# Water_Tank_V6_1_2020-12-28_12-10-16.net
KiCad netlist of a schematic drawn in EasyEDA
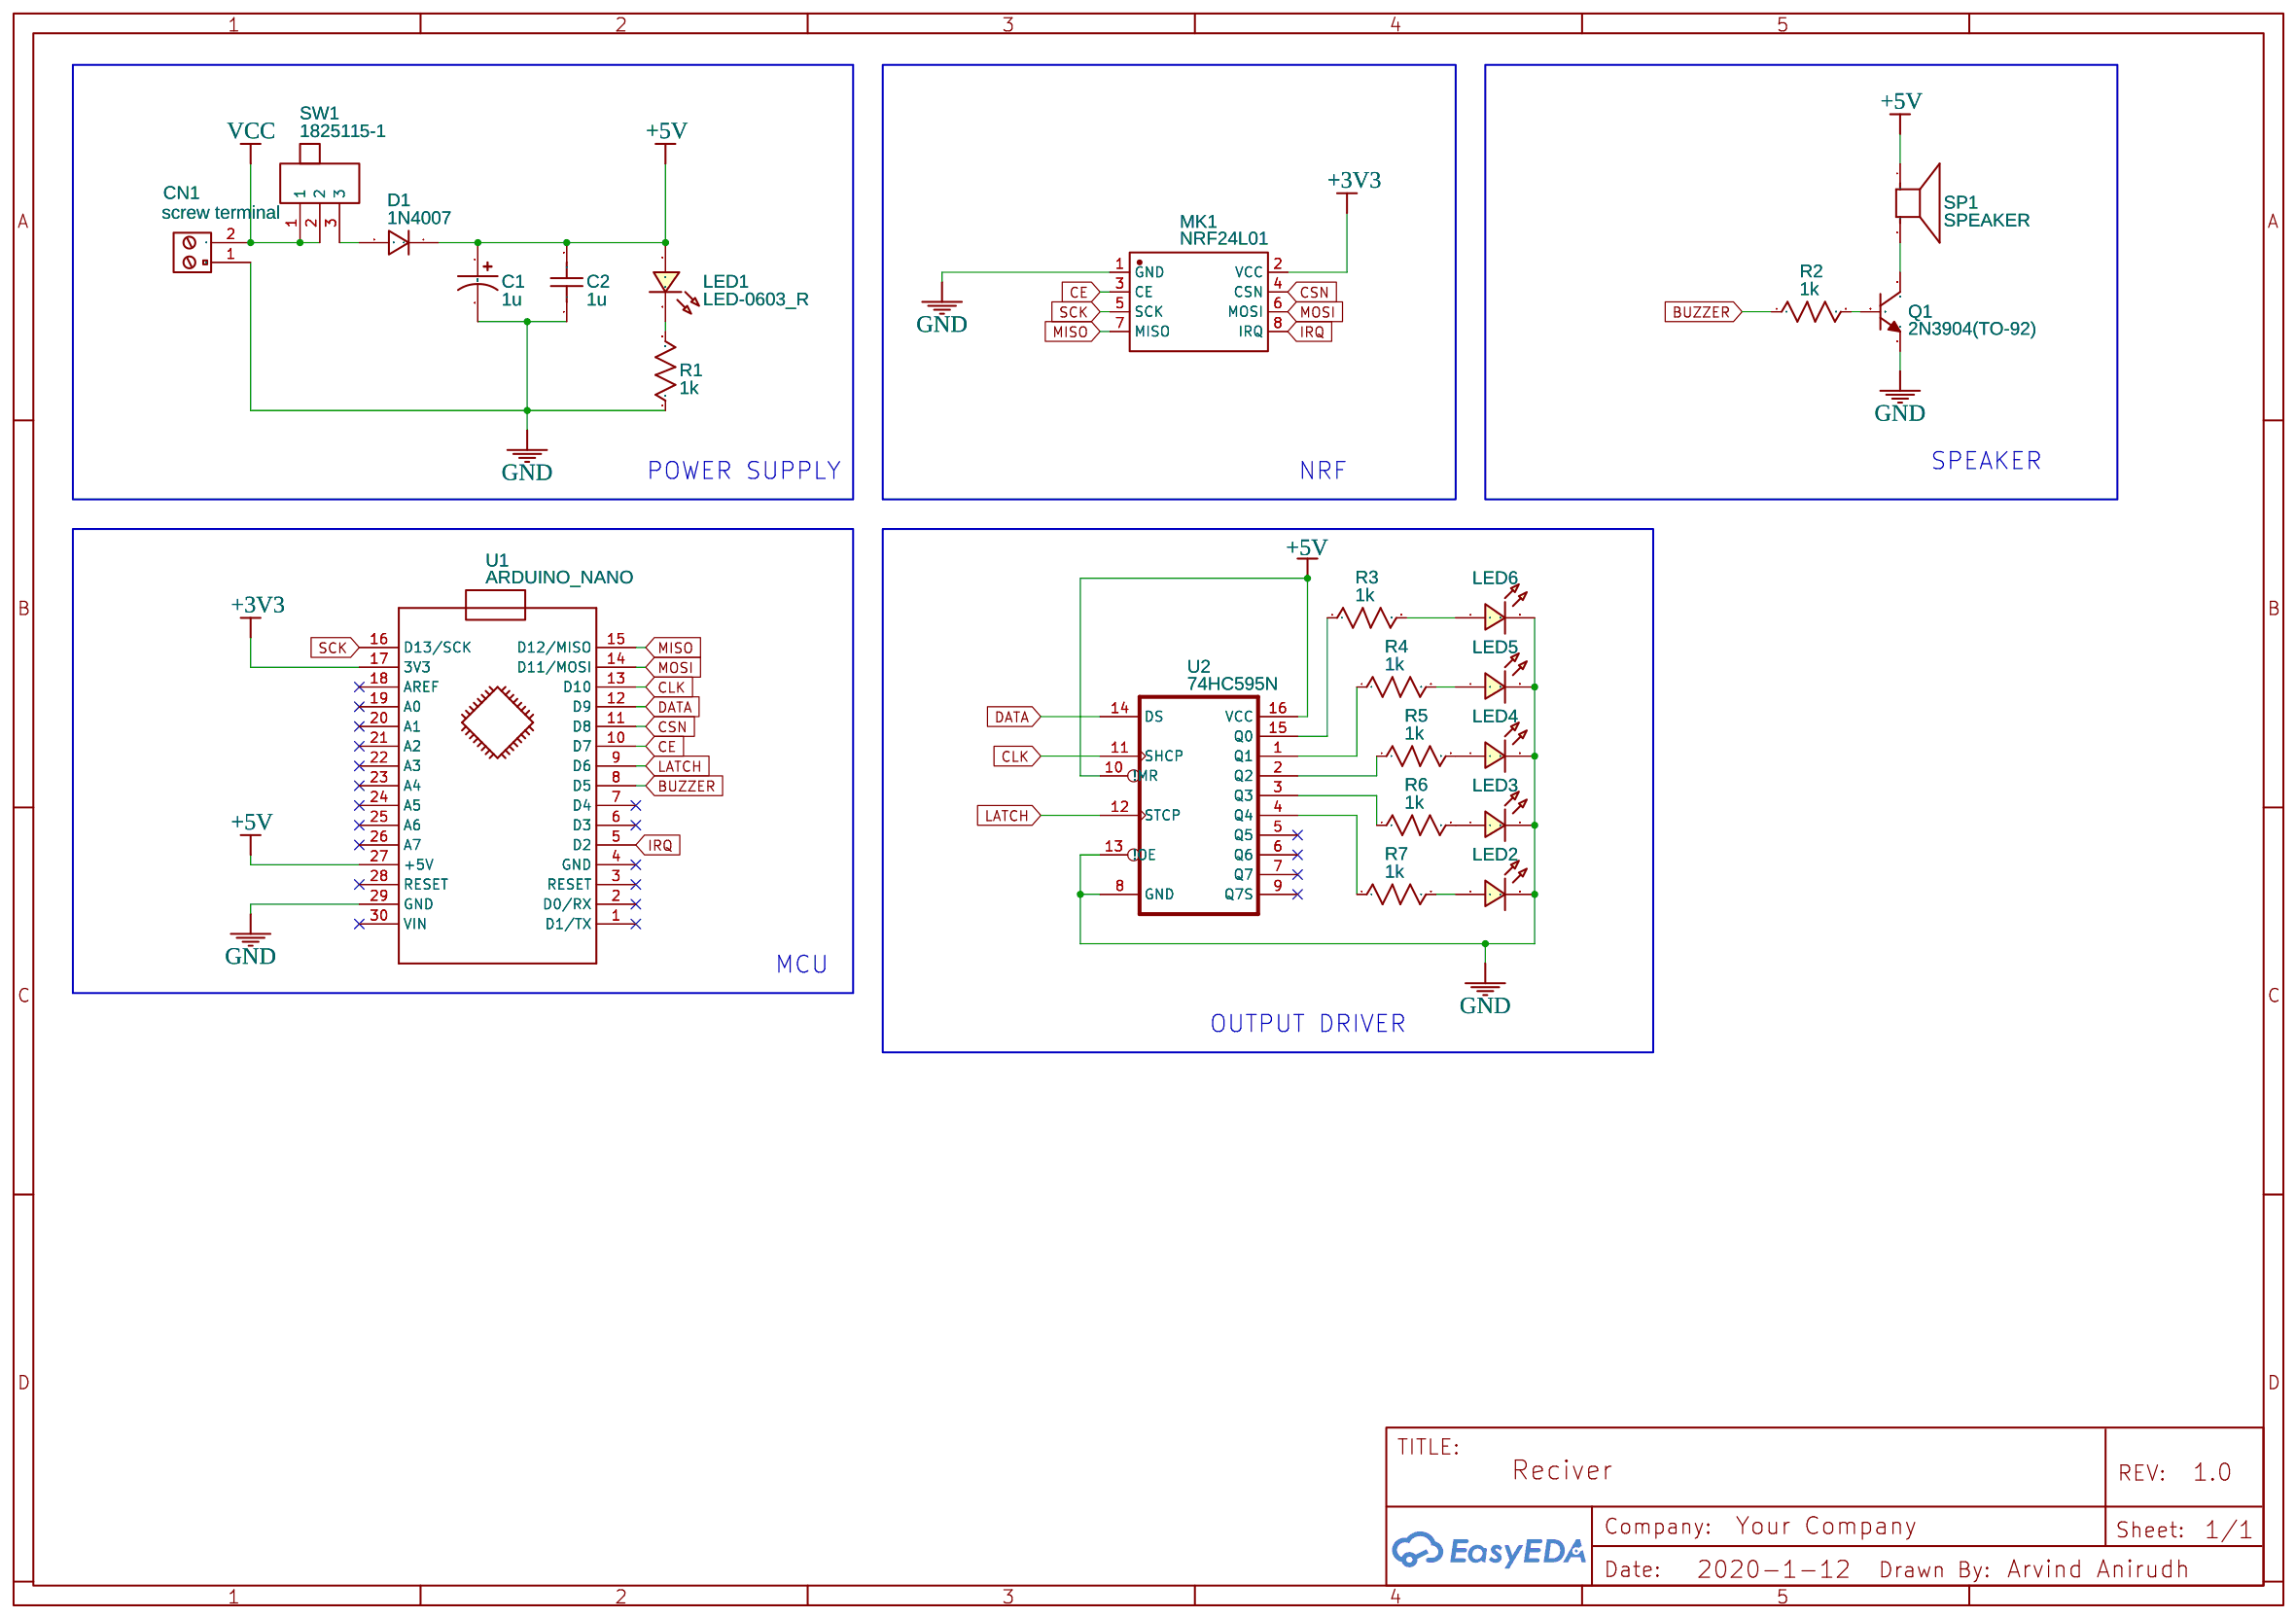
[diagram p0: Reciver]
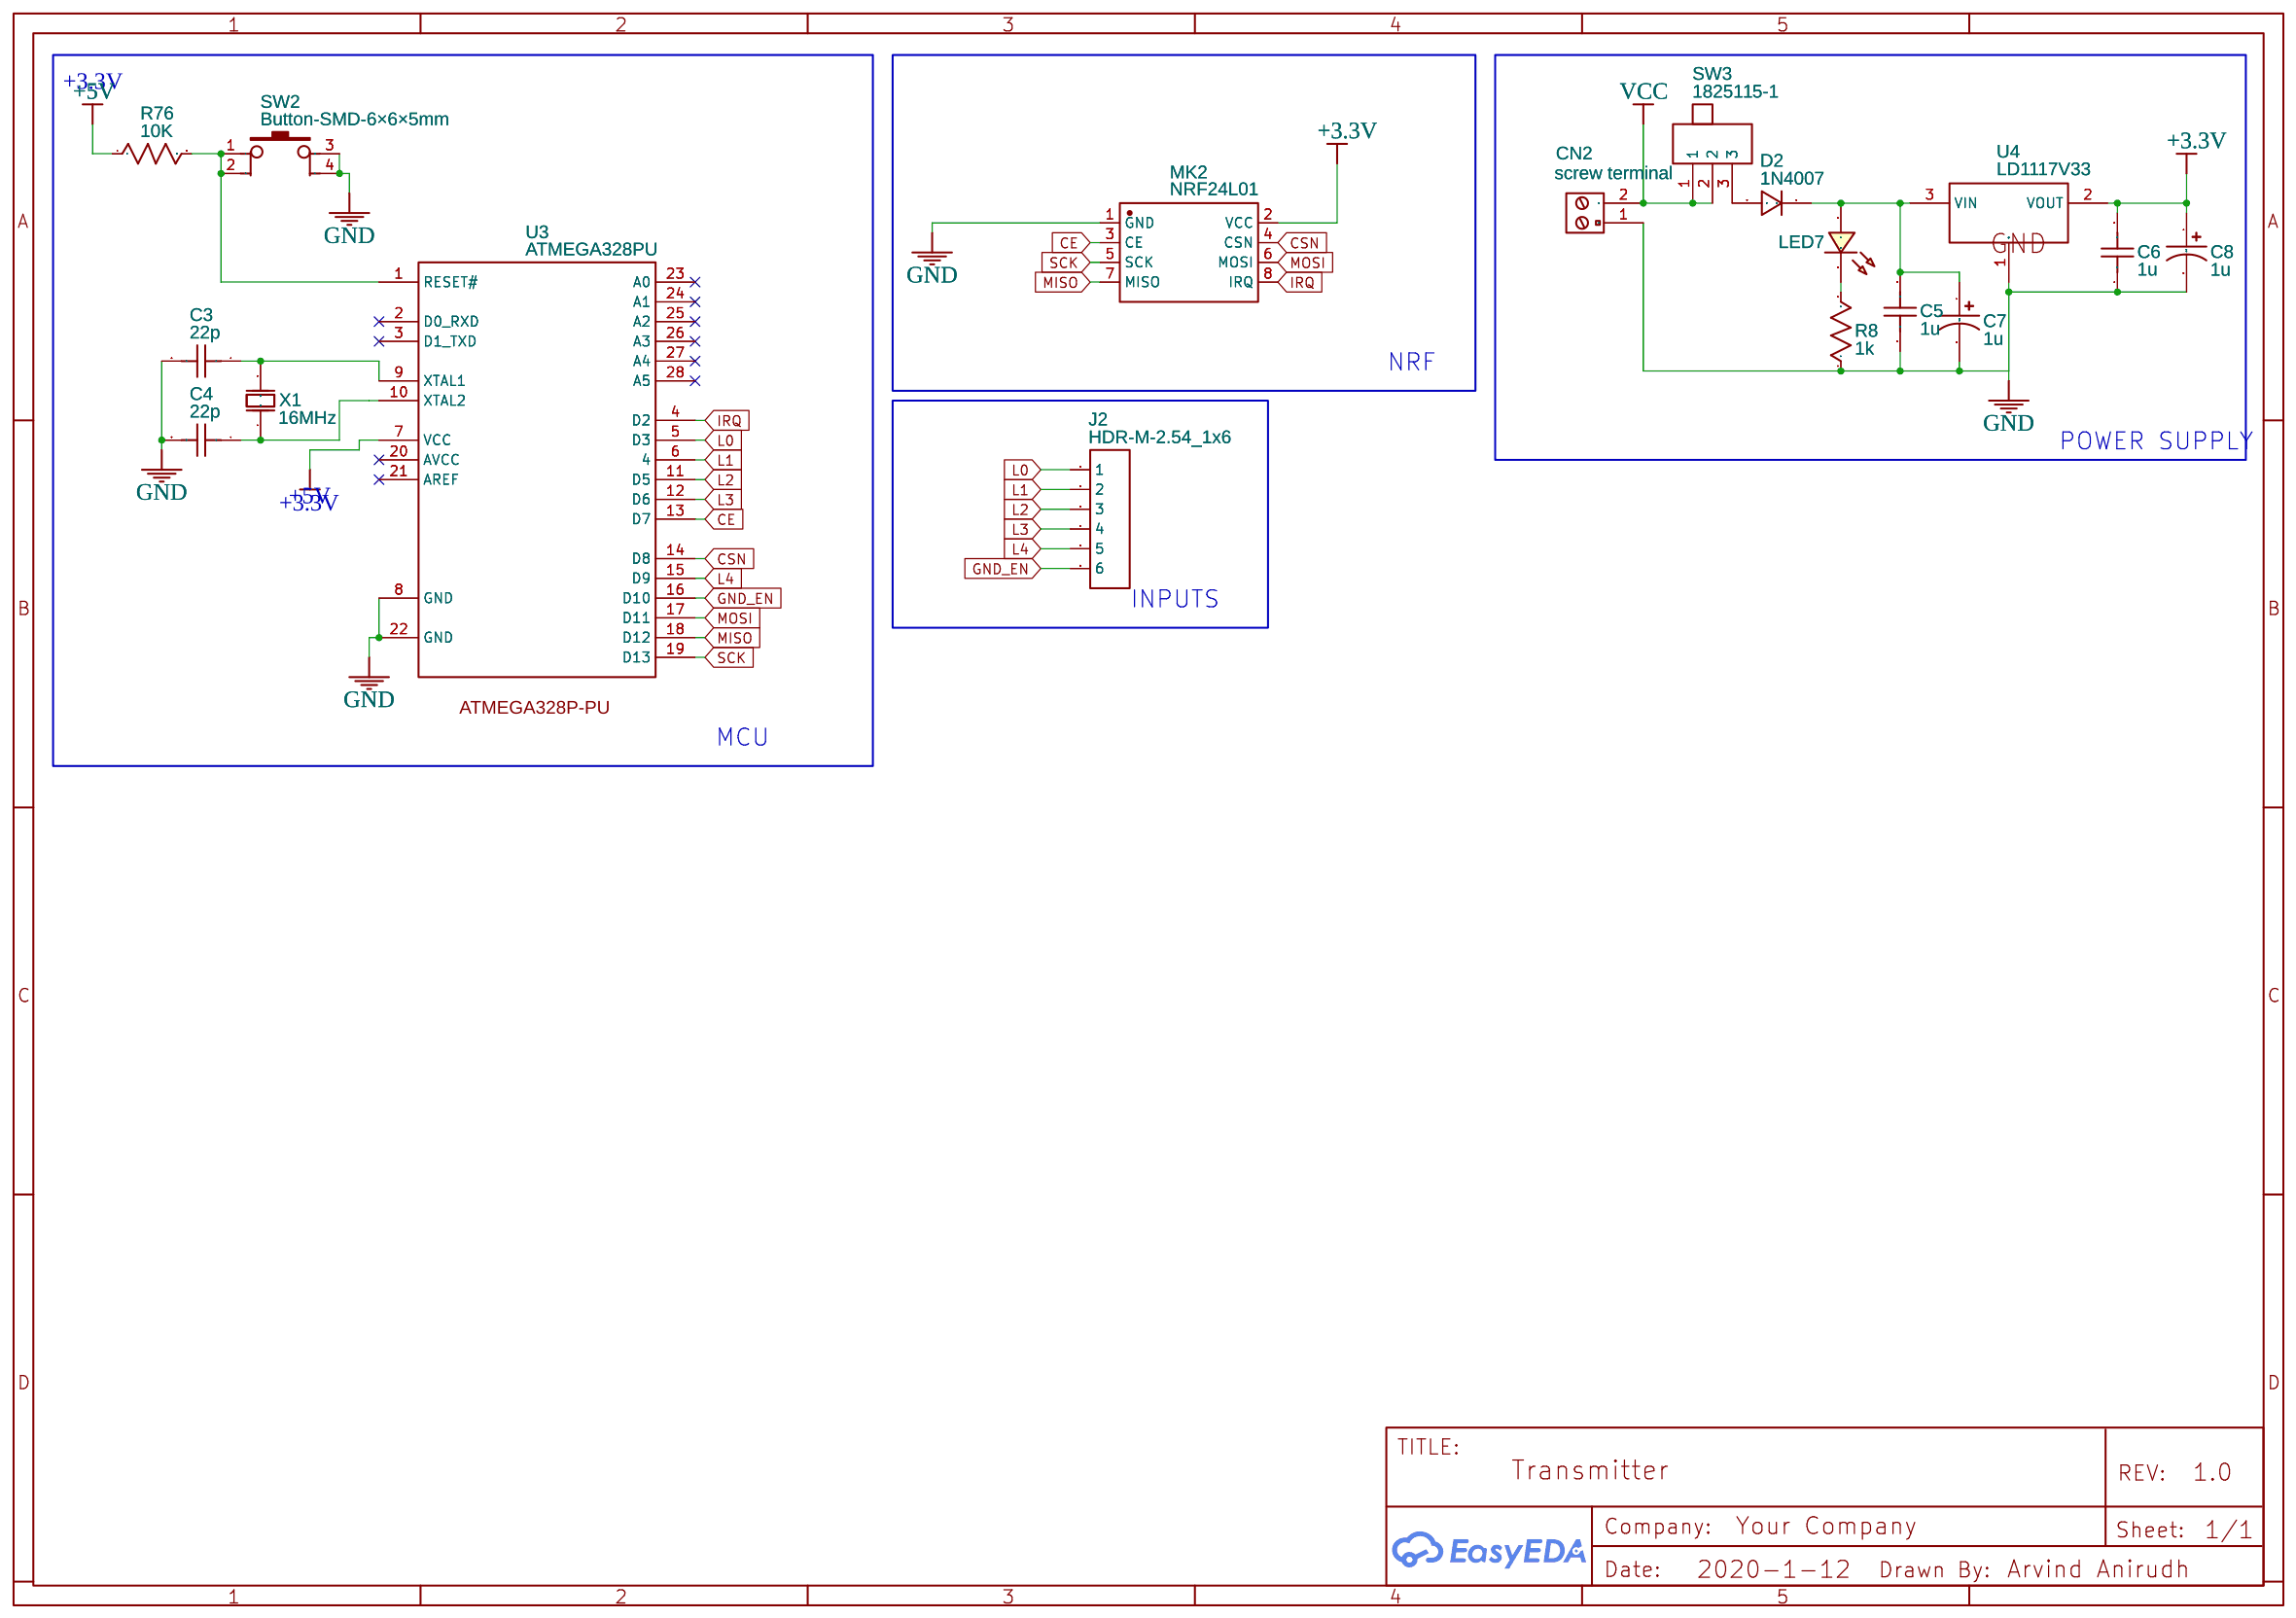
[diagram p1: Transmitter]

(export (version "E")
  (design (tool "Eeschema 10.0.6"))
  (components
    (comp (ref "C1") (value "1u") (libsource (lib "") (part "CE_TH_D4.0×F1.5_US")))
    (comp (ref "C2") (value "1u") (libsource (lib "") (part "C_RAD-0.1_US")))
    (comp (ref "CN1")
      (value "screw terminal")
      (fields (field (name "BOM_Supplier Part") "KF350-2P"))
      (libsource (lib "") (part "KF350-2P 3.5mm screw terminal"))
    )
    (comp (ref "D1")
      (value "1N4007")
      (fields (field (name "BOM_Supplier Part") "C106903"))
      (libsource (lib "") (part "1N4007"))
    )
    (comp (ref "LED1")
      (value "LED-0603_R")
      (fields
        (field (name "BOM_Manufacturer Part") "19-217/R6C-AL1M2VY/3T")
        (field (name "BOM_Supplier Part") "C72044")
      )
      (libsource (lib "") (part "LED-0603_R"))
    )
    (comp (ref "LED2")
      (value "LED-TH-3mm_R")
      (fields
        (field (name "BOM_Manufacturer Part") "204-10SDRD/S530-A3-L")
        (field (name "BOM_Supplier Part") "C84774")
      )
      (libsource (lib "") (part "LED-TH-3mm_R"))
    )
    (comp (ref "LED3")
      (value "LED-TH-3mm_G")
      (fields
        (field (name "BOM_Manufacturer Part") "204-10SYGD/S530-E3")
        (field (name "BOM_Supplier Part") "C85161")
      )
      (libsource (lib "") (part "LED-TH-3mm_G"))
    )
    (comp (ref "LED4")
      (value "LED-TH-3mm_G")
      (fields
        (field (name "BOM_Manufacturer Part") "204-10SYGD/S530-E3")
        (field (name "BOM_Supplier Part") "C85161")
      )
      (libsource (lib "") (part "LED-TH-3mm_G"))
    )
    (comp (ref "LED5")
      (value "LED-TH-3mm_G")
      (fields
        (field (name "BOM_Manufacturer Part") "204-10SYGD/S530-E3")
        (field (name "BOM_Supplier Part") "C85161")
      )
      (libsource (lib "") (part "LED-TH-3mm_G"))
    )
    (comp (ref "LED6")
      (value "LED-TH-3mm_B")
      (fields
        (field (name "BOM_Manufacturer Part") "204-10SUBC/S400-A4")
        (field (name "BOM_Supplier Part") "C86881")
      )
      (libsource (lib "") (part "LED-TH-3mm_B"))
    )
    (comp (ref "MK1")
      (value "NRF24L01")
      (fields
        (field (name "BOM_Manufacturer Part") "NRF24L01+功率加强版绑定2.4Gwireless module")
        (field (name "BOM_Supplier Part") "C90751")
      )
      (libsource (lib "") (part "NRF24L01"))
    )
    (comp (ref "Q1")
      (value "2N3904(TO-92)")
      (fields (field (name "BOM_Manufacturer Part") "2N3904") (field (name "BOM_Supplier Part") "C118538"))
      (libsource (lib "") (part "2N3904(TO-92)"))
    )
    (comp (ref "R1") (value "1k") (libsource (lib "") (part "R_AXIAL-0.4_US_1")))
    (comp (ref "R2") (value "1k") (libsource (lib "") (part "R_AXIAL-0.4_US")))
    (comp (ref "R3") (value "1k") (libsource (lib "") (part "R_AXIAL-0.4_US")))
    (comp (ref "R4") (value "1k") (libsource (lib "") (part "R_AXIAL-0.4_US")))
    (comp (ref "R5") (value "1k") (libsource (lib "") (part "R_AXIAL-0.4_US")))
    (comp (ref "R6") (value "1k") (libsource (lib "") (part "R_AXIAL-0.4_US")))
    (comp (ref "R7") (value "1k") (libsource (lib "") (part "R_AXIAL-0.4_US")))
    (comp (ref "SP1") (value "SPEAKER") (libsource (lib "") (part "SPEAKER")))
    (comp (ref "SW1")
      (value "1825115-1")
      (fields (field (name "BOM_Supplier Part") "C266201"))
      (libsource (lib "") (part "1825115-1"))
    )
    (comp (ref "U1") (value "ARDUINO_NANO") (libsource (lib "") (part "ARDUINO_NANO")))
    (comp (ref "U2") (value "74HC595N") (libsource (lib "") (part "74HC595N")))
    (comp (ref "C3") (value "22p") (libsource (lib "") (part "C_RAD-0.1_US_1")))
    (comp (ref "C4") (value "22p") (libsource (lib "") (part "C_RAD-0.1_US_1")))
    (comp (ref "C5") (value "1u") (libsource (lib "") (part "C_RAD-0.1_US")))
    (comp (ref "C6") (value "1u") (libsource (lib "") (part "C_RAD-0.1_US")))
    (comp (ref "C7") (value "1u") (libsource (lib "") (part "CE_TH_D4.0×F1.5_US")))
    (comp (ref "C8") (value "1u") (libsource (lib "") (part "CE_TH_D4.0×F1.5_US_1")))
    (comp (ref "CN2")
      (value "screw terminal")
      (fields (field (name "BOM_Supplier Part") "KF350-2P"))
      (libsource (lib "") (part "KF350-2P 3.5mm screw terminal"))
    )
    (comp (ref "D2")
      (value "1N4007")
      (fields (field (name "BOM_Supplier Part") "C106903"))
      (libsource (lib "") (part "1N4007"))
    )
    (comp (ref "J2")
      (value "HDR-M-2.54_1x6")
      (fields (field (name "BOM_Supplier Part") "C190819"))
      (libsource (lib "") (part "HDR-M-2.54_1x6"))
    )
    (comp (ref "LED7")
      (value "LED-0603_R")
      (fields
        (field (name "BOM_Manufacturer Part") "19-217/R6C-AL1M2VY/3T")
        (field (name "BOM_Supplier Part") "C72044")
      )
      (libsource (lib "") (part "LED-0603_R"))
    )
    (comp (ref "MK2")
      (value "NRF24L01")
      (fields
        (field (name "BOM_Manufacturer Part") "NRF24L01+功率加强版绑定2.4Gwireless module")
        (field (name "BOM_Supplier Part") "C90751")
      )
      (libsource (lib "") (part "NRF24L01"))
    )
    (comp (ref "R8") (value "1k") (libsource (lib "") (part "R_AXIAL-0.4_US")))
    (comp (ref "R76") (value "10K") (libsource (lib "") (part "Res_0805(1/8W)_US")))
    (comp (ref "SW2")
      (value "Button-SMD-6×6×5mm")
      (fields
        (field (name "BOM_Manufacturer Part") "6×6×5mm RHOS")
        (field (name "BOM_Supplier Part") "C21456")
      )
      (libsource (lib "") (part "Button-SMD-6×6×5mm"))
    )
    (comp (ref "SW3")
      (value "1825115-1")
      (fields (field (name "BOM_Supplier Part") "C266201"))
      (libsource (lib "") (part "1825115-1"))
    )
    (comp (ref "U3")
      (value "ATMEGA328PU")
      (fields
        (field (name "BOM_Manufacturer Part") "ATMEGA328P-PU")
        (field (name "BOM_Supplier Part") "C33901")
      )
      (libsource (lib "") (part "ATMEGA328PU"))
    )
    (comp (ref "U4")
      (value "LD1117V33")
      (fields (field (name "BOM_Supplier Part") "C283467"))
      (libsource (lib "") (part "LD1117V33"))
    )
    (comp (ref "X1")
      (value "16MHz")
      (fields
        (field (name "BOM_Manufacturer Part") "X49SD16MSB2SI")
        (field (name "BOM_Supplier Part") "C188202")
      )
      (libsource (lib "") (part "X49SD16MSB2SI"))
    )
  )
  (nets
    (net (code "1") (name "+3.3V") (class "Default")
      (node (ref "C6") (pin "2") (pinfunction "2_2") (pintype "unspecified"))
      (node (ref "C8") (pin "1") (pinfunction "1_1") (pintype "unspecified"))
      (node (ref "MK2") (pin "2") (pinfunction "VCC_2") (pintype "unspecified"))
      (node (ref "U4") (pin "2") (pinfunction "VOUT_2") (pintype "passive"))
    )
    (net (code "2") (name "+3V3") (class "Default")
      (node (ref "MK1") (pin "2") (pinfunction "VCC_2") (pintype "unspecified"))
      (node (ref "U1") (pin "17") (pinfunction "3V3_17") (pintype "unspecified"))
    )
    (net (code "3") (name "+5V") (class "Default")
      (node (ref "C1") (pin "1") (pinfunction "1_1") (pintype "unspecified"))
      (node (ref "C2") (pin "2") (pinfunction "2_2") (pintype "unspecified"))
      (node (ref "D1") (pin "1") (pinfunction "1_1") (pintype "unspecified"))
      (node (ref "LED1") (pin "1") (pinfunction "1_1") (pintype "unspecified"))
      (node (ref "R76") (pin "1") (pinfunction "1_1") (pintype "unspecified"))
      (node (ref "SP1") (pin "1") (pinfunction "+_1") (pintype "unspecified"))
      (node (ref "U1") (pin "27") (pinfunction "+5V_27") (pintype "unspecified"))
      (node (ref "U2") (pin "10") (pinfunction "!MR_10") (pintype "input"))
      (node (ref "U2") (pin "16") (pinfunction "VCC_16") (pintype "passive"))
      (node (ref "U3") (pin "7") (pinfunction "VCC_7") (pintype "passive"))
    )
    (net (code "4") (name "BUZZER") (class "Default")
      (node (ref "R2") (pin "1") (pinfunction "1_1") (pintype "unspecified"))
      (node (ref "U1") (pin "8") (pinfunction "D5_8") (pintype "unspecified"))
    )
    (net (code "5") (name "CE") (class "Default")
      (node (ref "MK1") (pin "3") (pinfunction "CE_3") (pintype "unspecified"))
      (node (ref "MK2") (pin "3") (pinfunction "CE_3") (pintype "unspecified"))
      (node (ref "U1") (pin "10") (pinfunction "D7_10") (pintype "unspecified"))
      (node (ref "U3") (pin "13") (pinfunction "D7_13") (pintype "bidirectional"))
    )
    (net (code "6") (name "CLK") (class "Default")
      (node (ref "U1") (pin "13") (pinfunction "D10_13") (pintype "unspecified"))
      (node (ref "U2") (pin "11") (pinfunction "SHCP_11") (pintype "input"))
    )
    (net (code "7") (name "CSN") (class "Default")
      (node (ref "MK1") (pin "4") (pinfunction "CSN_4") (pintype "unspecified"))
      (node (ref "MK2") (pin "4") (pinfunction "CSN_4") (pintype "unspecified"))
      (node (ref "U1") (pin "11") (pinfunction "D8_11") (pintype "unspecified"))
      (node (ref "U3") (pin "14") (pinfunction "D8_14") (pintype "bidirectional"))
    )
    (net (code "8") (name "DATA") (class "Default")
      (node (ref "U1") (pin "12") (pinfunction "D9_12") (pintype "unspecified"))
      (node (ref "U2") (pin "14") (pinfunction "DS_14") (pintype "input"))
    )
    (net (code "9") (name "GND") (class "Default")
      (node (ref "C1") (pin "2") (pinfunction "2_2") (pintype "unspecified"))
      (node (ref "C2") (pin "1") (pinfunction "1_1") (pintype "unspecified"))
      (node (ref "C3") (pin "2") (pinfunction "2_2") (pintype "unspecified"))
      (node (ref "C4") (pin "2") (pinfunction "2_2") (pintype "unspecified"))
      (node (ref "C5") (pin "1") (pinfunction "1_1") (pintype "unspecified"))
      (node (ref "C6") (pin "1") (pinfunction "1_1") (pintype "unspecified"))
      (node (ref "C7") (pin "2") (pinfunction "2_2") (pintype "unspecified"))
      (node (ref "C8") (pin "2") (pinfunction "2_2") (pintype "unspecified"))
      (node (ref "CN1") (pin "1") (pinfunction "1_1") (pintype "unspecified"))
      (node (ref "CN2") (pin "1") (pinfunction "1_1") (pintype "unspecified"))
      (node (ref "LED2") (pin "2") (pinfunction "2_2") (pintype "unspecified"))
      (node (ref "LED3") (pin "2") (pinfunction "2_2") (pintype "unspecified"))
      (node (ref "LED4") (pin "2") (pinfunction "2_2") (pintype "unspecified"))
      (node (ref "LED5") (pin "2") (pinfunction "2_2") (pintype "unspecified"))
      (node (ref "LED6") (pin "2") (pinfunction "2_2") (pintype "unspecified"))
      (node (ref "MK1") (pin "1") (pinfunction "GND_1") (pintype "unspecified"))
      (node (ref "MK2") (pin "1") (pinfunction "GND_1") (pintype "unspecified"))
      (node (ref "Q1") (pin "1") (pinfunction "E_1") (pintype "unspecified"))
      (node (ref "R1") (pin "1") (pinfunction "1_1") (pintype "unspecified"))
      (node (ref "R8") (pin "1") (pinfunction "1_1") (pintype "unspecified"))
      (node (ref "SW2") (pin "3") (pinfunction "3_3") (pintype "input"))
      (node (ref "SW2") (pin "4") (pinfunction "4_4") (pintype "input"))
      (node (ref "U1") (pin "29") (pinfunction "GND_29") (pintype "unspecified"))
      (node (ref "U2") (pin "13") (pinfunction "!OE_13") (pintype "input"))
      (node (ref "U2") (pin "8") (pinfunction "GND_8") (pintype "passive"))
      (node (ref "U3") (pin "22") (pinfunction "GND_22") (pintype "passive"))
      (node (ref "U3") (pin "8") (pinfunction "GND_8") (pintype "passive"))
      (node (ref "U4") (pin "1") (pinfunction "GND_1") (pintype "unspecified"))
    )
    (net (code "10") (name "GND_EN") (class "Default")
      (node (ref "J2") (pin "6") (pinfunction "6_6") (pintype "input"))
      (node (ref "U3") (pin "16") (pinfunction "D10_16") (pintype "bidirectional"))
    )
    (net (code "11") (name "IRQ") (class "Default")
      (node (ref "MK1") (pin "8") (pinfunction "IRQ_8") (pintype "unspecified"))
      (node (ref "MK2") (pin "8") (pinfunction "IRQ_8") (pintype "unspecified"))
      (node (ref "U1") (pin "5") (pinfunction "D2_5") (pintype "unspecified"))
      (node (ref "U3") (pin "4") (pinfunction "D2_4") (pintype "bidirectional"))
    )
    (net (code "12") (name "L0") (class "Default")
      (node (ref "J2") (pin "1") (pinfunction "1_1") (pintype "input"))
      (node (ref "U3") (pin "5") (pinfunction "D3_5") (pintype "bidirectional"))
    )
    (net (code "13") (name "L1") (class "Default")
      (node (ref "J2") (pin "2") (pinfunction "2_2") (pintype "input"))
      (node (ref "U3") (pin "6") (pinfunction "4_6") (pintype "bidirectional"))
    )
    (net (code "14") (name "L2") (class "Default")
      (node (ref "J2") (pin "3") (pinfunction "3_3") (pintype "input"))
      (node (ref "U3") (pin "11") (pinfunction "D5_11") (pintype "bidirectional"))
    )
    (net (code "15") (name "L3") (class "Default")
      (node (ref "J2") (pin "4") (pinfunction "4_4") (pintype "input"))
      (node (ref "U3") (pin "12") (pinfunction "D6_12") (pintype "bidirectional"))
    )
    (net (code "16") (name "L4") (class "Default")
      (node (ref "J2") (pin "5") (pinfunction "5_5") (pintype "input"))
      (node (ref "U3") (pin "15") (pinfunction "D9_15") (pintype "bidirectional"))
    )
    (net (code "17") (name "LATCH") (class "Default")
      (node (ref "U1") (pin "9") (pinfunction "D6_9") (pintype "unspecified"))
      (node (ref "U2") (pin "12") (pinfunction "STCP_12") (pintype "input"))
    )
    (net (code "18") (name "MISO") (class "Default")
      (node (ref "MK1") (pin "7") (pinfunction "MISO_7") (pintype "unspecified"))
      (node (ref "MK2") (pin "7") (pinfunction "MISO_7") (pintype "unspecified"))
      (node (ref "U1") (pin "15") (pinfunction "D12/MISO_15") (pintype "unspecified"))
      (node (ref "U3") (pin "18") (pinfunction "D12_18") (pintype "bidirectional"))
    )
    (net (code "19") (name "MOSI") (class "Default")
      (node (ref "MK1") (pin "6") (pinfunction "MOSI_6") (pintype "unspecified"))
      (node (ref "MK2") (pin "6") (pinfunction "MOSI_6") (pintype "unspecified"))
      (node (ref "U1") (pin "14") (pinfunction "D11/MOSI_14") (pintype "unspecified"))
      (node (ref "U3") (pin "17") (pinfunction "D11_17") (pintype "bidirectional"))
    )
    (net (code "20") (name "Net-(D1-Pad2)") (class "Default")
      (node (ref "D1") (pin "2") (pinfunction "2_2") (pintype "unspecified"))
      (node (ref "SW1") (pin "3") (pinfunction "3_3") (pintype "unspecified"))
    )
    (net (code "21") (name "Net-(D2-Pad2)") (class "Default")
      (node (ref "D2") (pin "2") (pinfunction "2_2") (pintype "unspecified"))
      (node (ref "SW3") (pin "3") (pinfunction "3_3") (pintype "unspecified"))
    )
    (net (code "22") (name "Net-(LED1-Pad2)") (class "Default")
      (node (ref "LED1") (pin "2") (pinfunction "2_2") (pintype "unspecified"))
      (node (ref "R1") (pin "2") (pinfunction "2_2") (pintype "unspecified"))
    )
    (net (code "23") (name "Net-(LED2-Pad1)") (class "Default")
      (node (ref "LED2") (pin "1") (pinfunction "1_1") (pintype "unspecified"))
      (node (ref "R7") (pin "2") (pinfunction "2_2") (pintype "unspecified"))
    )
    (net (code "24") (name "Net-(LED3-Pad1)") (class "Default")
      (node (ref "LED3") (pin "1") (pinfunction "1_1") (pintype "unspecified"))
      (node (ref "R6") (pin "2") (pinfunction "2_2") (pintype "unspecified"))
    )
    (net (code "25") (name "Net-(LED4-Pad1)") (class "Default")
      (node (ref "LED4") (pin "1") (pinfunction "1_1") (pintype "unspecified"))
      (node (ref "R5") (pin "2") (pinfunction "2_2") (pintype "unspecified"))
    )
    (net (code "26") (name "Net-(LED5-Pad1)") (class "Default")
      (node (ref "LED5") (pin "1") (pinfunction "1_1") (pintype "unspecified"))
      (node (ref "R4") (pin "2") (pinfunction "2_2") (pintype "unspecified"))
    )
    (net (code "27") (name "Net-(LED6-Pad1)") (class "Default")
      (node (ref "LED6") (pin "1") (pinfunction "1_1") (pintype "unspecified"))
      (node (ref "R3") (pin "2") (pinfunction "2_2") (pintype "unspecified"))
    )
    (net (code "28") (name "Net-(LED7-Pad2)") (class "Default")
      (node (ref "LED7") (pin "2") (pinfunction "2_2") (pintype "unspecified"))
      (node (ref "R8") (pin "2") (pinfunction "2_2") (pintype "unspecified"))
    )
    (net (code "29") (name "Net-(Q1-B)") (class "Default")
      (node (ref "Q1") (pin "2") (pinfunction "B_2") (pintype "unspecified"))
      (node (ref "R2") (pin "2") (pinfunction "2_2") (pintype "unspecified"))
    )
    (net (code "30") (name "Net-(Q1-C)") (class "Default")
      (node (ref "Q1") (pin "3") (pinfunction "C_3") (pintype "unspecified"))
      (node (ref "SP1") (pin "2") (pinfunction "-_2") (pintype "unspecified"))
    )
    (net (code "31") (name "Net-(U2-Q0)") (class "Default")
      (node (ref "R3") (pin "1") (pinfunction "1_1") (pintype "unspecified"))
      (node (ref "U2") (pin "15") (pinfunction "Q0_15") (pintype "unspecified"))
    )
    (net (code "32") (name "Net-(U2-Q1)") (class "Default")
      (node (ref "R4") (pin "1") (pinfunction "1_1") (pintype "unspecified"))
      (node (ref "U2") (pin "1") (pinfunction "Q1_1") (pintype "unspecified"))
    )
    (net (code "33") (name "Net-(U2-Q2)") (class "Default")
      (node (ref "R5") (pin "1") (pinfunction "1_1") (pintype "unspecified"))
      (node (ref "U2") (pin "2") (pinfunction "Q2_2") (pintype "unspecified"))
    )
    (net (code "34") (name "Net-(U2-Q3)") (class "Default")
      (node (ref "R6") (pin "1") (pinfunction "1_1") (pintype "unspecified"))
      (node (ref "U2") (pin "3") (pinfunction "Q3_3") (pintype "unspecified"))
    )
    (net (code "35") (name "Net-(U2-Q4)") (class "Default")
      (node (ref "R7") (pin "1") (pinfunction "1_1") (pintype "unspecified"))
      (node (ref "U2") (pin "4") (pinfunction "Q4_4") (pintype "unspecified"))
    )
    (net (code "36") (name "Net-(U3-RESET#)") (class "Default")
      (node (ref "R76") (pin "2") (pinfunction "2_2") (pintype "unspecified"))
      (node (ref "SW2") (pin "1") (pinfunction "1_1") (pintype "input"))
      (node (ref "SW2") (pin "2") (pinfunction "2_2") (pintype "input"))
      (node (ref "U3") (pin "1") (pinfunction "RESET#_1") (pintype "bidirectional"))
    )
    (net (code "37") (name "Net-(U3-XTAL1)") (class "Default")
      (node (ref "C3") (pin "1") (pinfunction "1_1") (pintype "unspecified"))
      (node (ref "U3") (pin "9") (pinfunction "XTAL1_9") (pintype "bidirectional"))
      (node (ref "X1") (pin "2") (pinfunction "OSC2_2") (pintype "input"))
    )
    (net (code "38") (name "Net-(U3-XTAL2)") (class "Default")
      (node (ref "C4") (pin "1") (pinfunction "1_1") (pintype "unspecified"))
      (node (ref "U3") (pin "10") (pinfunction "XTAL2_10") (pintype "bidirectional"))
      (node (ref "X1") (pin "1") (pinfunction "OSC1_1") (pintype "input"))
    )
    (net (code "39") (name "Net-(U4-VIN)") (class "Default")
      (node (ref "C5") (pin "2") (pinfunction "2_2") (pintype "unspecified"))
      (node (ref "C7") (pin "1") (pinfunction "1_1") (pintype "unspecified"))
      (node (ref "D2") (pin "1") (pinfunction "1_1") (pintype "unspecified"))
      (node (ref "LED7") (pin "1") (pinfunction "1_1") (pintype "unspecified"))
      (node (ref "U4") (pin "3") (pinfunction "VIN_3") (pintype "passive"))
    )
    (net (code "40") (name "SCK") (class "Default")
      (node (ref "MK1") (pin "5") (pinfunction "SCK_5") (pintype "unspecified"))
      (node (ref "MK2") (pin "5") (pinfunction "SCK_5") (pintype "unspecified"))
      (node (ref "U1") (pin "16") (pinfunction "D13/SCK_16") (pintype "unspecified"))
      (node (ref "U3") (pin "19") (pinfunction "D13_19") (pintype "bidirectional"))
    )
    (net (code "41") (name "VCC") (class "Default")
      (node (ref "CN1") (pin "2") (pinfunction "2_2") (pintype "unspecified"))
      (node (ref "CN2") (pin "2") (pinfunction "2_2") (pintype "unspecified"))
      (node (ref "SW1") (pin "1") (pinfunction "1_1") (pintype "unspecified"))
      (node (ref "SW1") (pin "2") (pinfunction "2_2") (pintype "unspecified"))
      (node (ref "SW3") (pin "1") (pinfunction "1_1") (pintype "unspecified"))
      (node (ref "SW3") (pin "2") (pinfunction "2_2") (pintype "unspecified"))
    )
    (net (code "42") (name "unconnected-(U1-A0-Pad19)") (class "Default")
      (node (ref "U1") (pin "19") (pinfunction "A0_19") (pintype "unspecified+no_connect"))
    )
    (net (code "43") (name "unconnected-(U1-A1-Pad20)") (class "Default")
      (node (ref "U1") (pin "20") (pinfunction "A1_20") (pintype "unspecified+no_connect"))
    )
    (net (code "44") (name "unconnected-(U1-A2-Pad21)") (class "Default")
      (node (ref "U1") (pin "21") (pinfunction "A2_21") (pintype "unspecified+no_connect"))
    )
    (net (code "45") (name "unconnected-(U1-A3-Pad22)") (class "Default")
      (node (ref "U1") (pin "22") (pinfunction "A3_22") (pintype "unspecified+no_connect"))
    )
    (net (code "46") (name "unconnected-(U1-A4-Pad23)") (class "Default")
      (node (ref "U1") (pin "23") (pinfunction "A4_23") (pintype "unspecified+no_connect"))
    )
    (net (code "47") (name "unconnected-(U1-A5-Pad24)") (class "Default")
      (node (ref "U1") (pin "24") (pinfunction "A5_24") (pintype "unspecified+no_connect"))
    )
    (net (code "48") (name "unconnected-(U1-A6-Pad25)") (class "Default")
      (node (ref "U1") (pin "25") (pinfunction "A6_25") (pintype "unspecified+no_connect"))
    )
    (net (code "49") (name "unconnected-(U1-A7-Pad26)") (class "Default")
      (node (ref "U1") (pin "26") (pinfunction "A7_26") (pintype "unspecified+no_connect"))
    )
    (net (code "50") (name "unconnected-(U1-AREF-Pad18)") (class "Default")
      (node (ref "U1") (pin "18") (pinfunction "AREF_18") (pintype "unspecified+no_connect"))
    )
    (net (code "51") (name "unconnected-(U1-D0{slash}RX-Pad2)") (class "Default")
      (node (ref "U1") (pin "2") (pinfunction "D0/RX_2") (pintype "unspecified+no_connect"))
    )
    (net (code "52") (name "unconnected-(U1-D1{slash}TX-Pad1)") (class "Default")
      (node (ref "U1") (pin "1") (pinfunction "D1/TX_1") (pintype "unspecified+no_connect"))
    )
    (net (code "53") (name "unconnected-(U1-D3-Pad6)") (class "Default")
      (node (ref "U1") (pin "6") (pinfunction "D3_6") (pintype "unspecified+no_connect"))
    )
    (net (code "54") (name "unconnected-(U1-D4-Pad7)") (class "Default")
      (node (ref "U1") (pin "7") (pinfunction "D4_7") (pintype "unspecified+no_connect"))
    )
    (net (code "55") (name "unconnected-(U1-GND-Pad4)") (class "Default")
      (node (ref "U1") (pin "4") (pinfunction "GND_4") (pintype "unspecified+no_connect"))
    )
    (net (code "56") (name "unconnected-(U1-RESET-Pad3)") (class "Default")
      (node (ref "U1") (pin "3") (pinfunction "RESET_3") (pintype "unspecified+no_connect"))
    )
    (net (code "57") (name "unconnected-(U1-RESET-Pad28)") (class "Default")
      (node (ref "U1") (pin "28") (pinfunction "RESET_28") (pintype "unspecified+no_connect"))
    )
    (net (code "58") (name "unconnected-(U1-VIN-Pad30)") (class "Default")
      (node (ref "U1") (pin "30") (pinfunction "VIN_30") (pintype "unspecified+no_connect"))
    )
    (net (code "59") (name "unconnected-(U2-Q5-Pad5)") (class "Default")
      (node (ref "U2") (pin "5") (pinfunction "Q5_5") (pintype "unspecified+no_connect"))
    )
    (net (code "60") (name "unconnected-(U2-Q6-Pad6)") (class "Default")
      (node (ref "U2") (pin "6") (pinfunction "Q6_6") (pintype "unspecified+no_connect"))
    )
    (net (code "61") (name "unconnected-(U2-Q7-Pad7)") (class "Default")
      (node (ref "U2") (pin "7") (pinfunction "Q7_7") (pintype "unspecified+no_connect"))
    )
    (net (code "62") (name "unconnected-(U2-Q7S-Pad9)") (class "Default")
      (node (ref "U2") (pin "9") (pinfunction "Q7S_9") (pintype "unspecified+no_connect"))
    )
    (net (code "63") (name "unconnected-(U3-A0-Pad23)") (class "Default")
      (node (ref "U3") (pin "23") (pinfunction "A0_23") (pintype "bidirectional+no_connect"))
    )
    (net (code "64") (name "unconnected-(U3-A1-Pad24)") (class "Default")
      (node (ref "U3") (pin "24") (pinfunction "A1_24") (pintype "bidirectional+no_connect"))
    )
    (net (code "65") (name "unconnected-(U3-A2-Pad25)") (class "Default")
      (node (ref "U3") (pin "25") (pinfunction "A2_25") (pintype "bidirectional+no_connect"))
    )
    (net (code "66") (name "unconnected-(U3-A3-Pad26)") (class "Default")
      (node (ref "U3") (pin "26") (pinfunction "A3_26") (pintype "bidirectional+no_connect"))
    )
    (net (code "67") (name "unconnected-(U3-A4-Pad27)") (class "Default")
      (node (ref "U3") (pin "27") (pinfunction "A4_27") (pintype "bidirectional+no_connect"))
    )
    (net (code "68") (name "unconnected-(U3-A5-Pad28)") (class "Default")
      (node (ref "U3") (pin "28") (pinfunction "A5_28") (pintype "bidirectional+no_connect"))
    )
    (net (code "69") (name "unconnected-(U3-AREF-Pad21)") (class "Default")
      (node (ref "U3") (pin "21") (pinfunction "AREF_21") (pintype "passive+no_connect"))
    )
    (net (code "70") (name "unconnected-(U3-AVCC-Pad20)") (class "Default")
      (node (ref "U3") (pin "20") (pinfunction "AVCC_20") (pintype "passive+no_connect"))
    )
    (net (code "71") (name "unconnected-(U3-D0_RXD-Pad2)") (class "Default")
      (node (ref "U3") (pin "2") (pinfunction "D0_RXD_2") (pintype "bidirectional+no_connect"))
    )
    (net (code "72") (name "unconnected-(U3-D1_TXD-Pad3)") (class "Default")
      (node (ref "U3") (pin "3") (pinfunction "D1_TXD_3") (pintype "bidirectional+no_connect"))
    )
  )
)
